# Powerboard_Conector_1.net
KiCad netlist of a schematic drawn in Altium Designer
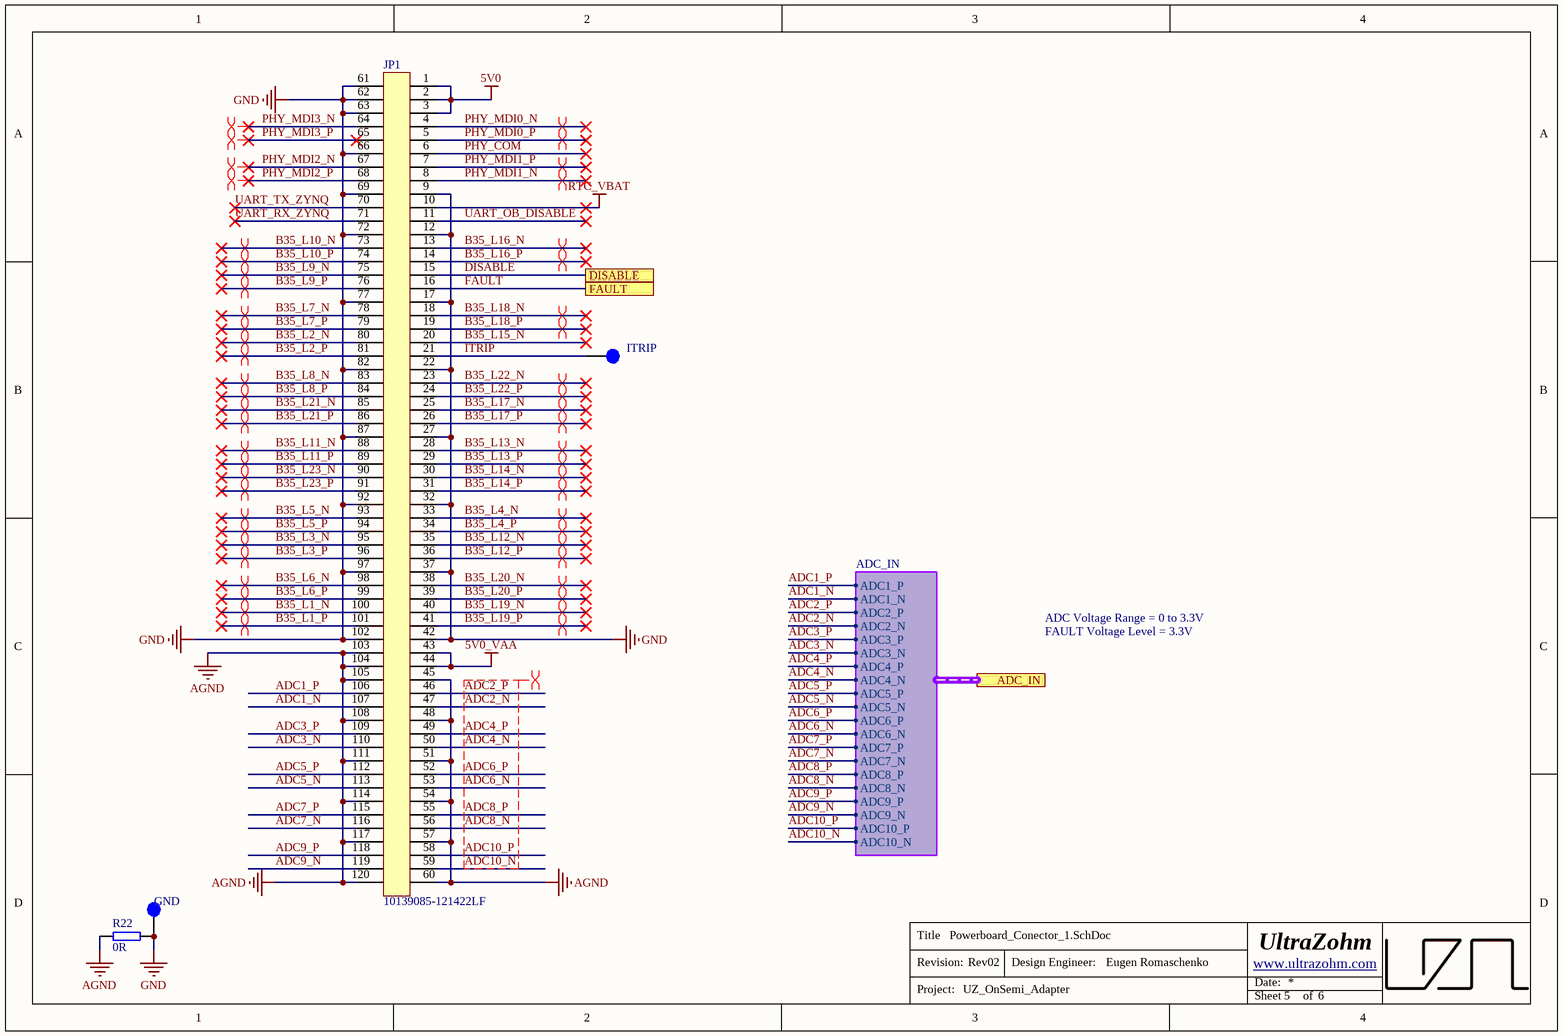
[diagram p0: Powerboard_Conector_1.SchDoc]

(export (version "E")
  (design (tool "Eeschema 10.0.6"))
  (components
    (comp (ref "GND")
      (value "GND")
      (footprint "TP_1mm")
      (description "Testpoint 1mm")
      (fields (field (name "CREATED") "2018_06_25_AGeiger"))
      (libsource (lib "UltraZOhm_CarrierBoard") (part "TP_1mm"))
    )
    (comp (ref "ITRIP")
      (value "ITRIP")
      (footprint "TP_1mm")
      (description "Testpoint 1mm")
      (fields (field (name "CREATED") "2018_06_25_AGeiger"))
      (libsource (lib "UltraZOhm_CarrierBoard") (part "TP_1mm"))
    )
    (comp (ref "JP1")
      (value "10139085-121422LF")
      (footprint "10139085-121422LF")
      (description "Bergstack+ 0.8mm pich - 120pin B2B connector")
      (fields (field (name "PUBLISHER") "Amphenol ICC"))
      (libsource (lib "connectors_testpoints") (part "10139085-121422LF"))
    )
    (comp (ref "R22")
      (value "0R")
      (footprint "RESC1608X06N")
      (fields
        (field (name "MF") "Vishay / Dale")
        (field (name "MPN") "CRCW06031M00FKEAC")
        (field (name "TOLERANCE") "1%")
      )
      (libsource (lib "UltraZohm_ADC") (part "R_0603"))
    )
  )
  (nets
    (net (code "2") (name "/ADC1_N") (class "Default") (node (ref "JP1") (pin "107") (pintype "passive")))
    (net (code "3") (name "/ADC1_P") (class "Default") (node (ref "JP1") (pin "106") (pintype "passive")))
    (net (code "4") (name "/ADC2_N") (class "Default") (node (ref "JP1") (pin "47") (pintype "passive")))
    (net (code "5") (name "/ADC2_P") (class "Default") (node (ref "JP1") (pin "46") (pintype "passive")))
    (net (code "6") (name "/ADC3_N") (class "Default") (node (ref "JP1") (pin "110") (pintype "passive")))
    (net (code "7") (name "/ADC3_P") (class "Default") (node (ref "JP1") (pin "109") (pintype "passive")))
    (net (code "8") (name "/ADC4_N") (class "Default") (node (ref "JP1") (pin "50") (pintype "passive")))
    (net (code "9") (name "/ADC4_P") (class "Default") (node (ref "JP1") (pin "49") (pintype "passive")))
    (net (code "10") (name "/ADC5_N") (class "Default") (node (ref "JP1") (pin "113") (pintype "passive")))
    (net (code "11") (name "/ADC5_P") (class "Default") (node (ref "JP1") (pin "112") (pintype "passive")))
    (net (code "12") (name "/ADC6_N") (class "Default") (node (ref "JP1") (pin "53") (pintype "passive")))
    (net (code "13") (name "/ADC6_P") (class "Default") (node (ref "JP1") (pin "52") (pintype "passive")))
    (net (code "14") (name "/ADC7_N") (class "Default") (node (ref "JP1") (pin "116") (pintype "passive")))
    (net (code "15") (name "/ADC7_P") (class "Default") (node (ref "JP1") (pin "115") (pintype "passive")))
    (net (code "16") (name "/ADC8_N") (class "Default") (node (ref "JP1") (pin "56") (pintype "passive")))
    (net (code "17") (name "/ADC8_P") (class "Default") (node (ref "JP1") (pin "55") (pintype "passive")))
    (net (code "18") (name "/ADC9_N") (class "Default") (node (ref "JP1") (pin "119") (pintype "passive")))
    (net (code "19") (name "/ADC9_P") (class "Default") (node (ref "JP1") (pin "118") (pintype "passive")))
    (net (code "20") (name "/ADC10_N") (class "Default") (node (ref "JP1") (pin "59") (pintype "passive")))
    (net (code "21") (name "/ADC10_P") (class "Default") (node (ref "JP1") (pin "58") (pintype "passive")))
    (net (code "22") (name "/B35_L1_N") (class "Default")
      (node (ref "JP1") (pin "100") (pintype "passive+no_connect"))
    )
    (net (code "23") (name "/B35_L1_P") (class "Default")
      (node (ref "JP1") (pin "101") (pintype "passive+no_connect"))
    )
    (net (code "24") (name "/B35_L2_N") (class "Default")
      (node (ref "JP1") (pin "80") (pintype "passive+no_connect"))
    )
    (net (code "25") (name "/B35_L2_P") (class "Default")
      (node (ref "JP1") (pin "81") (pintype "passive+no_connect"))
    )
    (net (code "26") (name "/B35_L3_N") (class "Default")
      (node (ref "JP1") (pin "95") (pintype "passive+no_connect"))
    )
    (net (code "27") (name "/B35_L3_P") (class "Default")
      (node (ref "JP1") (pin "96") (pintype "passive+no_connect"))
    )
    (net (code "28") (name "/B35_L4_N") (class "Default")
      (node (ref "JP1") (pin "33") (pintype "passive+no_connect"))
    )
    (net (code "29") (name "/B35_L4_P") (class "Default")
      (node (ref "JP1") (pin "34") (pintype "passive+no_connect"))
    )
    (net (code "30") (name "/B35_L5_N") (class "Default")
      (node (ref "JP1") (pin "93") (pintype "passive+no_connect"))
    )
    (net (code "31") (name "/B35_L5_P") (class "Default")
      (node (ref "JP1") (pin "94") (pintype "passive+no_connect"))
    )
    (net (code "32") (name "/B35_L6_N") (class "Default")
      (node (ref "JP1") (pin "98") (pintype "passive+no_connect"))
    )
    (net (code "33") (name "/B35_L6_P") (class "Default")
      (node (ref "JP1") (pin "99") (pintype "passive+no_connect"))
    )
    (net (code "34") (name "/B35_L7_N") (class "Default")
      (node (ref "JP1") (pin "78") (pintype "passive+no_connect"))
    )
    (net (code "35") (name "/B35_L7_P") (class "Default")
      (node (ref "JP1") (pin "79") (pintype "passive+no_connect"))
    )
    (net (code "36") (name "/B35_L8_N") (class "Default")
      (node (ref "JP1") (pin "83") (pintype "passive+no_connect"))
    )
    (net (code "37") (name "/B35_L8_P") (class "Default")
      (node (ref "JP1") (pin "84") (pintype "passive+no_connect"))
    )
    (net (code "38") (name "/B35_L9_N") (class "Default")
      (node (ref "JP1") (pin "75") (pintype "passive+no_connect"))
    )
    (net (code "39") (name "/B35_L9_P") (class "Default")
      (node (ref "JP1") (pin "76") (pintype "passive+no_connect"))
    )
    (net (code "40") (name "/B35_L10_N") (class "Default")
      (node (ref "JP1") (pin "73") (pintype "passive+no_connect"))
    )
    (net (code "41") (name "/B35_L10_P") (class "Default")
      (node (ref "JP1") (pin "74") (pintype "passive+no_connect"))
    )
    (net (code "42") (name "/B35_L11_N") (class "Default")
      (node (ref "JP1") (pin "88") (pintype "passive+no_connect"))
    )
    (net (code "43") (name "/B35_L11_P") (class "Default")
      (node (ref "JP1") (pin "89") (pintype "passive+no_connect"))
    )
    (net (code "44") (name "/B35_L12_N") (class "Default")
      (node (ref "JP1") (pin "35") (pintype "passive+no_connect"))
    )
    (net (code "45") (name "/B35_L12_P") (class "Default")
      (node (ref "JP1") (pin "36") (pintype "passive+no_connect"))
    )
    (net (code "46") (name "/B35_L13_N") (class "Default")
      (node (ref "JP1") (pin "28") (pintype "passive+no_connect"))
    )
    (net (code "47") (name "/B35_L13_P") (class "Default")
      (node (ref "JP1") (pin "29") (pintype "passive+no_connect"))
    )
    (net (code "48") (name "/B35_L14_N") (class "Default")
      (node (ref "JP1") (pin "30") (pintype "passive+no_connect"))
    )
    (net (code "49") (name "/B35_L14_P") (class "Default")
      (node (ref "JP1") (pin "31") (pintype "passive+no_connect"))
    )
    (net (code "50") (name "/B35_L15_N") (class "Default")
      (node (ref "JP1") (pin "20") (pintype "passive+no_connect"))
    )
    (net (code "51") (name "/B35_L16_N") (class "Default")
      (node (ref "JP1") (pin "13") (pintype "passive+no_connect"))
    )
    (net (code "52") (name "/B35_L16_P") (class "Default")
      (node (ref "JP1") (pin "14") (pintype "passive+no_connect"))
    )
    (net (code "53") (name "/B35_L17_N") (class "Default")
      (node (ref "JP1") (pin "25") (pintype "passive+no_connect"))
    )
    (net (code "54") (name "/B35_L17_P") (class "Default")
      (node (ref "JP1") (pin "26") (pintype "passive+no_connect"))
    )
    (net (code "55") (name "/B35_L18_N") (class "Default")
      (node (ref "JP1") (pin "18") (pintype "passive+no_connect"))
    )
    (net (code "56") (name "/B35_L18_P") (class "Default")
      (node (ref "JP1") (pin "19") (pintype "passive+no_connect"))
    )
    (net (code "57") (name "/B35_L19_N") (class "Default")
      (node (ref "JP1") (pin "40") (pintype "passive+no_connect"))
    )
    (net (code "58") (name "/B35_L19_P") (class "Default")
      (node (ref "JP1") (pin "41") (pintype "passive+no_connect"))
    )
    (net (code "59") (name "/B35_L20_N") (class "Default")
      (node (ref "JP1") (pin "38") (pintype "passive+no_connect"))
    )
    (net (code "60") (name "/B35_L20_P") (class "Default")
      (node (ref "JP1") (pin "39") (pintype "passive+no_connect"))
    )
    (net (code "61") (name "/B35_L21_N") (class "Default")
      (node (ref "JP1") (pin "85") (pintype "passive+no_connect"))
    )
    (net (code "62") (name "/B35_L21_P") (class "Default")
      (node (ref "JP1") (pin "86") (pintype "passive+no_connect"))
    )
    (net (code "63") (name "/B35_L22_N") (class "Default")
      (node (ref "JP1") (pin "23") (pintype "passive+no_connect"))
    )
    (net (code "64") (name "/B35_L22_P") (class "Default")
      (node (ref "JP1") (pin "24") (pintype "passive+no_connect"))
    )
    (net (code "65") (name "/B35_L23_N") (class "Default")
      (node (ref "JP1") (pin "90") (pintype "passive+no_connect"))
    )
    (net (code "66") (name "/B35_L23_P") (class "Default")
      (node (ref "JP1") (pin "91") (pintype "passive+no_connect"))
    )
    (net (code "67") (name "/DISABLE") (class "Default") (node (ref "JP1") (pin "15") (pintype "passive")))
    (net (code "68") (name "/FAULT") (class "Default") (node (ref "JP1") (pin "16") (pintype "passive")))
    (net (code "69") (name "/ITRIP") (class "Default")
      (node (ref "ITRIP") (pin "1") (pintype "passive"))
      (node (ref "JP1") (pin "21") (pintype "passive"))
    )
    (net (code "70") (name "/PHY_COM") (class "Default")
      (node (ref "JP1") (pin "6") (pintype "passive+no_connect"))
    )
    (net (code "71") (name "/PHY_MDI0_N") (class "Default")
      (node (ref "JP1") (pin "4") (pintype "passive+no_connect"))
    )
    (net (code "72") (name "/PHY_MDI0_P") (class "Default")
      (node (ref "JP1") (pin "5") (pintype "passive+no_connect"))
    )
    (net (code "73") (name "/PHY_MDI1_N") (class "Default")
      (node (ref "JP1") (pin "8") (pintype "passive+no_connect"))
    )
    (net (code "74") (name "/PHY_MDI1_P") (class "Default")
      (node (ref "JP1") (pin "7") (pintype "passive+no_connect"))
    )
    (net (code "75") (name "/PHY_MDI2_N") (class "Default")
      (node (ref "JP1") (pin "67") (pintype "passive+no_connect"))
    )
    (net (code "76") (name "/PHY_MDI2_P") (class "Default")
      (node (ref "JP1") (pin "68") (pintype "passive+no_connect"))
    )
    (net (code "77") (name "/PHY_MDI3_N") (class "Default")
      (node (ref "JP1") (pin "64") (pintype "passive+no_connect"))
    )
    (net (code "78") (name "/PHY_MDI3_P") (class "Default")
      (node (ref "JP1") (pin "65") (pintype "passive+no_connect"))
    )
    (net (code "79") (name "/UART_OB_DISABLE") (class "Default")
      (node (ref "JP1") (pin "11") (pintype "passive+no_connect"))
    )
    (net (code "80") (name "/UART_RX_ZYNQ") (class "Default")
      (node (ref "JP1") (pin "71") (pintype "passive+no_connect"))
    )
    (net (code "81") (name "/UART_TX_ZYNQ") (class "Default")
      (node (ref "JP1") (pin "70") (pintype "passive+no_connect"))
    )
    (net (code "83") (name "5V0") (class "Default")
      (node (ref "JP1") (pin "1") (pintype "passive"))
      (node (ref "JP1") (pin "2") (pintype "passive"))
      (node (ref "JP1") (pin "3") (pintype "passive"))
    )
    (net (code "84") (name "5V0_VAA") (class "Default")
      (node (ref "JP1") (pin "43") (pintype "passive"))
      (node (ref "JP1") (pin "44") (pintype "passive"))
    )
    (net (code "85") (name "AGND") (class "Default")
      (node (ref "JP1") (pin "103") (pintype "passive"))
      (node (ref "JP1") (pin "104") (pintype "passive"))
      (node (ref "JP1") (pin "105") (pintype "passive"))
      (node (ref "JP1") (pin "108") (pintype "passive"))
      (node (ref "JP1") (pin "111") (pintype "passive"))
      (node (ref "JP1") (pin "114") (pintype "passive"))
      (node (ref "JP1") (pin "117") (pintype "passive"))
      (node (ref "JP1") (pin "120") (pintype "passive"))
      (node (ref "JP1") (pin "45") (pintype "passive"))
      (node (ref "JP1") (pin "48") (pintype "passive"))
      (node (ref "JP1") (pin "51") (pintype "passive"))
      (node (ref "JP1") (pin "54") (pintype "passive"))
      (node (ref "JP1") (pin "57") (pintype "passive"))
      (node (ref "JP1") (pin "60") (pintype "passive"))
      (node (ref "R22") (pin "2") (pintype "passive"))
    )
    (net (code "86") (name "GND") (class "Default")
      (node (ref "GND") (pin "1") (pintype "passive"))
      (node (ref "JP1") (pin "102") (pintype "passive"))
      (node (ref "JP1") (pin "12") (pintype "passive"))
      (node (ref "JP1") (pin "17") (pintype "passive"))
      (node (ref "JP1") (pin "22") (pintype "passive"))
      (node (ref "JP1") (pin "27") (pintype "passive"))
      (node (ref "JP1") (pin "32") (pintype "passive"))
      (node (ref "JP1") (pin "37") (pintype "passive"))
      (node (ref "JP1") (pin "42") (pintype "passive"))
      (node (ref "JP1") (pin "61") (pintype "passive"))
      (node (ref "JP1") (pin "62") (pintype "passive"))
      (node (ref "JP1") (pin "63") (pintype "passive"))
      (node (ref "JP1") (pin "66") (pintype "passive"))
      (node (ref "JP1") (pin "69") (pintype "passive"))
      (node (ref "JP1") (pin "72") (pintype "passive"))
      (node (ref "JP1") (pin "77") (pintype "passive"))
      (node (ref "JP1") (pin "82") (pintype "passive"))
      (node (ref "JP1") (pin "87") (pintype "passive"))
      (node (ref "JP1") (pin "9") (pintype "passive"))
      (node (ref "JP1") (pin "92") (pintype "passive"))
      (node (ref "JP1") (pin "97") (pintype "passive"))
      (node (ref "R22") (pin "1") (pintype "passive"))
    )
    (net (code "87") (name "RTC_VBAT") (class "Default") (node (ref "JP1") (pin "10") (pintype "passive")))
  )
)
